# Control.net
KiCad netlist of a schematic drawn in Altium Designer
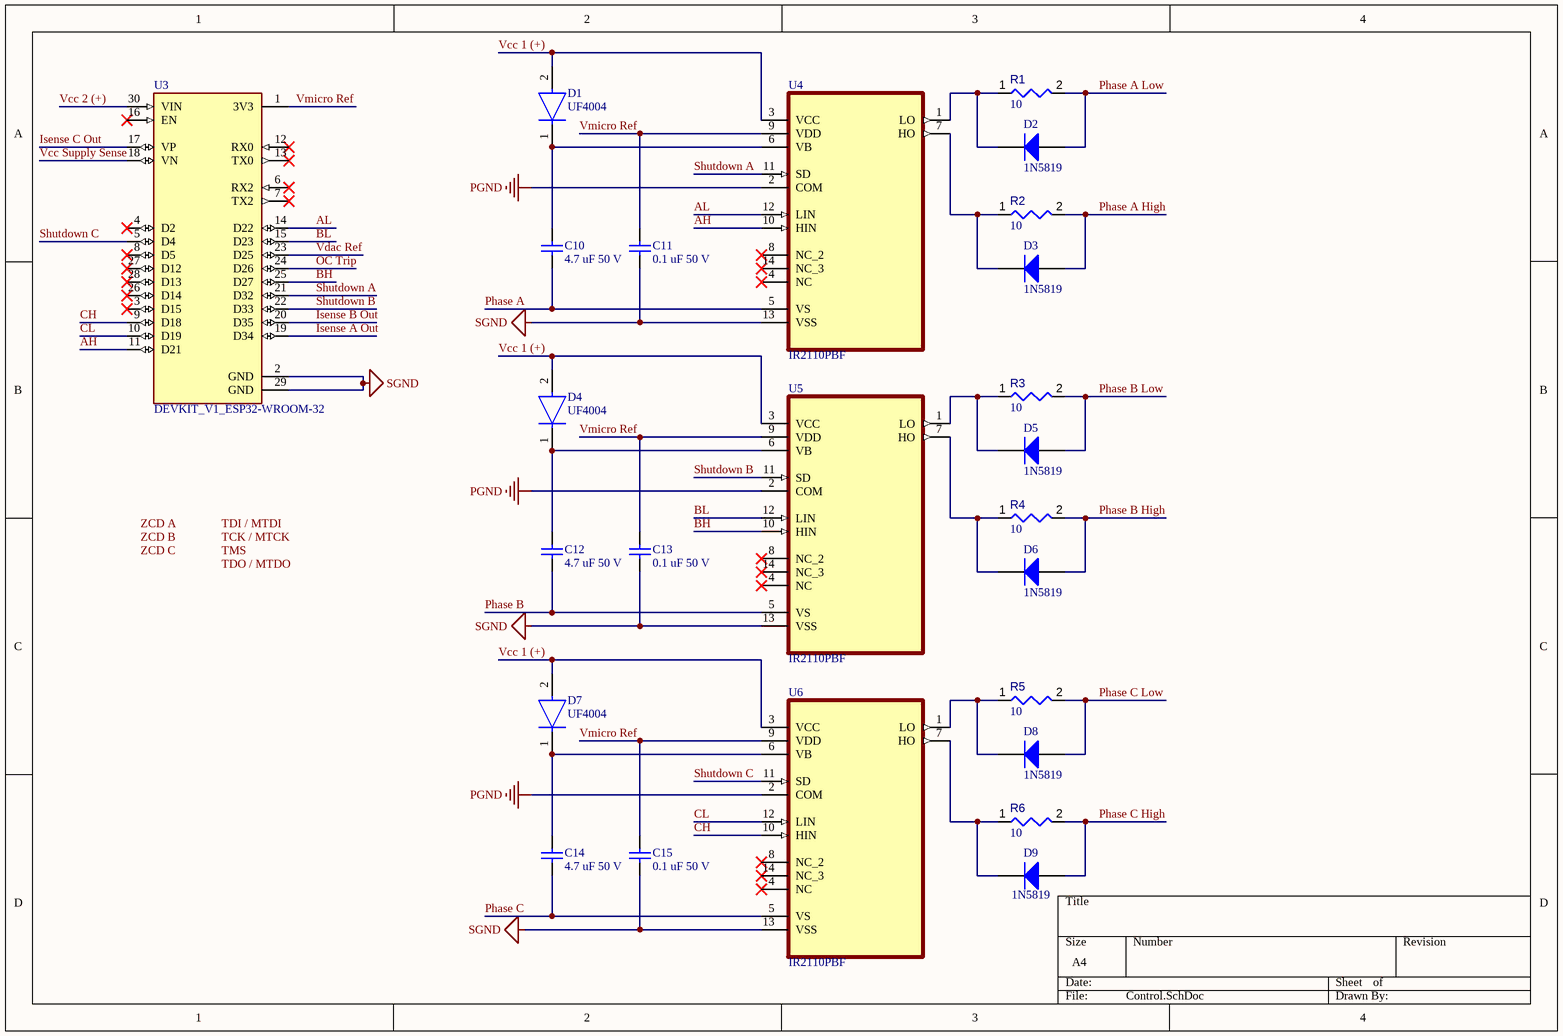
[diagram p0: Control.SchDoc]

(export (version "E")
  (design (tool "Eeschema 10.0.6"))
  (components
    (comp (ref "C10")
      (value "4.7 uF 50 V")
      (footprint "CAPR51-254-508X318X736")
      (libsource (lib "Altium Content Vault") (part "CAP-NP-2"))
    )
    (comp (ref "C11")
      (value "0.1 uF 50 V")
      (footprint "CAPR51-254-508X318X736")
      (libsource (lib "Altium Content Vault") (part "CAP-NP-2"))
    )
    (comp (ref "C12")
      (value "4.7 uF 50 V")
      (footprint "CAPR51-254-508X318X736")
      (libsource (lib "Altium Content Vault") (part "CAP-NP-2"))
    )
    (comp (ref "C13")
      (value "0.1 uF 50 V")
      (footprint "CAPR51-254-508X318X736")
      (libsource (lib "Altium Content Vault") (part "CAP-NP-2"))
    )
    (comp (ref "C14")
      (value "4.7 uF 50 V")
      (footprint "CAPR51-254-508X318X736")
      (libsource (lib "Altium Content Vault") (part "CAP-NP-2"))
    )
    (comp (ref "C15")
      (value "0.1 uF 50 V")
      (footprint "CAPR51-254-508X318X736")
      (libsource (lib "Altium Content Vault") (part "CAP-NP-2"))
    )
    (comp (ref "D1")
      (value "UF4004")
      (footprint "FP-017AH-MFG")
      (description "UF4004 Rectifier Diode, 1 Phase, 1 Element, 1A, 400V V(RRM), Silicon, DO-41")
      (libsource (lib "Altium Content Vault") (part "d7152d700b627762746794eb795d46e"))
    )
    (comp (ref "D2")
      (value "1N5819")
      (footprint "ONSC-AXIAL_LEAD-2-59-10_P")
      (description "Low Drop Power Schottky Rectifier, 40 V, 1 A, 2-Pin DO-41, RoHS")
      (fields (field (name "MANUFACTURER") "ON Semiconductor"))
      (libsource (lib "Pessoal") (part "D-AK-2"))
    )
    (comp (ref "D3")
      (value "1N5819")
      (footprint "ONSC-AXIAL_LEAD-2-59-10_P")
      (description "Low Drop Power Schottky Rectifier, 40 V, 1 A, 2-Pin DO-41, RoHS")
      (fields (field (name "MANUFACTURER") "ON Semiconductor"))
      (libsource (lib "Pessoal") (part "D-AK-2"))
    )
    (comp (ref "D4")
      (value "UF4004")
      (footprint "FP-017AH-MFG")
      (description "UF4004 Rectifier Diode, 1 Phase, 1 Element, 1A, 400V V(RRM), Silicon, DO-41")
      (libsource (lib "Altium Content Vault") (part "d7152d700b627762746794eb795d46e"))
    )
    (comp (ref "D5")
      (value "1N5819")
      (footprint "ONSC-AXIAL_LEAD-2-59-10_P")
      (description "Low Drop Power Schottky Rectifier, 40 V, 1 A, 2-Pin DO-41, RoHS")
      (fields (field (name "MANUFACTURER") "ON Semiconductor"))
      (libsource (lib "Pessoal") (part "D-AK-2"))
    )
    (comp (ref "D6")
      (value "1N5819")
      (footprint "ONSC-AXIAL_LEAD-2-59-10_P")
      (description "Low Drop Power Schottky Rectifier, 40 V, 1 A, 2-Pin DO-41, RoHS")
      (fields (field (name "MANUFACTURER") "ON Semiconductor"))
      (libsource (lib "Pessoal") (part "D-AK-2"))
    )
    (comp (ref "D7")
      (value "UF4004")
      (footprint "FP-017AH-MFG")
      (description "UF4004 Rectifier Diode, 1 Phase, 1 Element, 1A, 400V V(RRM), Silicon, DO-41")
      (libsource (lib "Altium Content Vault") (part "d7152d700b627762746794eb795d46e"))
    )
    (comp (ref "D8")
      (value "1N5819")
      (footprint "ONSC-AXIAL_LEAD-2-59-10_P")
      (description "Low Drop Power Schottky Rectifier, 40 V, 1 A, 2-Pin DO-41, RoHS")
      (fields (field (name "MANUFACTURER") "ON Semiconductor"))
      (libsource (lib "Pessoal") (part "D-AK-2"))
    )
    (comp (ref "D9")
      (value "1N5819")
      (footprint "ONSC-AXIAL_LEAD-2-59-10_P")
      (description "Low Drop Power Schottky Rectifier, 40 V, 1 A, 2-Pin DO-41, RoHS")
      (fields (field (name "MANUFACTURER") "ON Semiconductor"))
      (libsource (lib "Pessoal") (part "D-AK-2"))
    )
    (comp (ref "R1")
      (value "10")
      (footprint "RESA60-630X240")
      (description "10 Ohms ±1% 0.25W, 1/4W Through Hole Resistor Axial Metal Film")
      (fields (field (name "TOLERANCE") "1%") (field (name "POWER") "250mW"))
      (libsource (lib "Pessoal") (part "RES-2"))
    )
    (comp (ref "R2")
      (value "10")
      (footprint "RESA60-630X240")
      (description "10 Ohms ±1% 0.25W, 1/4W Through Hole Resistor Axial Metal Film")
      (fields (field (name "TOLERANCE") "1%") (field (name "POWER") "250mW"))
      (libsource (lib "Pessoal") (part "RES-2"))
    )
    (comp (ref "R3")
      (value "10")
      (footprint "RESA60-630X240")
      (description "10 Ohms ±1% 0.25W, 1/4W Through Hole Resistor Axial Metal Film")
      (fields (field (name "TOLERANCE") "1%") (field (name "POWER") "250mW"))
      (libsource (lib "Pessoal") (part "RES-2"))
    )
    (comp (ref "R4")
      (value "10")
      (footprint "RESA60-630X240")
      (description "10 Ohms ±1% 0.25W, 1/4W Through Hole Resistor Axial Metal Film")
      (fields (field (name "TOLERANCE") "1%") (field (name "POWER") "250mW"))
      (libsource (lib "Pessoal") (part "RES-2"))
    )
    (comp (ref "R5")
      (value "10")
      (footprint "RESA60-630X240")
      (description "10 Ohms ±1% 0.25W, 1/4W Through Hole Resistor Axial Metal Film")
      (fields (field (name "TOLERANCE") "1%") (field (name "POWER") "250mW"))
      (libsource (lib "Pessoal") (part "RES-2"))
    )
    (comp (ref "R6")
      (value "10")
      (footprint "RESA60-630X240")
      (description "10 Ohms ±1% 0.25W, 1/4W Through Hole Resistor Axial Metal Film")
      (fields (field (name "TOLERANCE") "1%") (field (name "POWER") "250mW"))
      (libsource (lib "Pessoal") (part "RES-2"))
    )
    (comp (ref "U3")
      (value "DEVKIT_V1_ESP32-WROOM-32")
      (footprint "MODULE_DEVKIT_V1_ESP32-WROOM-32")
      (description "WROOM-32 Development Board ESP32 ESP-32S WiFi Bluetooth Dev Module")
      (fields (field (name "MF") "Do it") (field (name "MP") "DEVKIT V1 ESP32-WROOM-32"))
      (libsource (lib "DEVKIT_V1_ESP32-WROOM-32") (part "DEVKIT_V1_ESP32-WROOM-32"))
    )
    (comp (ref "U4")
      (value "IR2110PBF")
      (footprint "DIP254P762X533-14")
      (fields (field (name "MF") "Infineon"))
      (libsource (lib "IR2110PBF") (part "IR2110PBF"))
    )
    (comp (ref "U5")
      (value "IR2110PBF")
      (footprint "DIP254P762X533-14")
      (fields (field (name "MF") "Infineon"))
      (libsource (lib "IR2110PBF") (part "IR2110PBF"))
    )
    (comp (ref "U6")
      (value "IR2110PBF")
      (footprint "DIP254P762X533-14")
      (fields (field (name "MF") "Infineon"))
      (libsource (lib "IR2110PBF") (part "IR2110PBF"))
    )
  )
  (nets
    (net (code "1") (name "/AH") (class "Default")
      (node (ref "U3") (pin "11") (pinfunction "D21_11") (pintype "bidirectional"))
      (node (ref "U4") (pin "10") (pinfunction "HIN_10") (pintype "input"))
    )
    (net (code "2") (name "/AL") (class "Default")
      (node (ref "U3") (pin "14") (pinfunction "D22_14") (pintype "bidirectional"))
      (node (ref "U4") (pin "12") (pinfunction "LIN_12") (pintype "input"))
    )
    (net (code "3") (name "/BH") (class "Default")
      (node (ref "U3") (pin "25") (pinfunction "D27_25") (pintype "bidirectional"))
      (node (ref "U5") (pin "10") (pinfunction "HIN_10") (pintype "input"))
    )
    (net (code "4") (name "/BL") (class "Default")
      (node (ref "U3") (pin "15") (pinfunction "D23_15") (pintype "bidirectional"))
      (node (ref "U5") (pin "12") (pinfunction "LIN_12") (pintype "input"))
    )
    (net (code "5") (name "/CH") (class "Default")
      (node (ref "U3") (pin "9") (pinfunction "D18_9") (pintype "bidirectional"))
      (node (ref "U6") (pin "10") (pinfunction "HIN_10") (pintype "input"))
    )
    (net (code "6") (name "/CL") (class "Default")
      (node (ref "U3") (pin "10") (pinfunction "D19_10") (pintype "bidirectional"))
      (node (ref "U6") (pin "12") (pinfunction "LIN_12") (pintype "input"))
    )
    (net (code "7") (name "/Isense A Out") (class "Default")
      (node (ref "U3") (pin "19") (pinfunction "D34_19") (pintype "bidirectional"))
    )
    (net (code "8") (name "/Isense B Out") (class "Default")
      (node (ref "U3") (pin "20") (pinfunction "D35_20") (pintype "bidirectional"))
    )
    (net (code "9") (name "/Isense C Out") (class "Default")
      (node (ref "U3") (pin "17") (pinfunction "VP_17") (pintype "bidirectional"))
    )
    (net (code "10") (name "/OC Trip") (class "Default")
      (node (ref "U3") (pin "24") (pinfunction "D26_24") (pintype "bidirectional"))
    )
    (net (code "11") (name "/Phase A") (class "Default")
      (node (ref "C10") (pin "1") (pinfunction "1_1") (pintype "passive"))
      (node (ref "U4") (pin "5") (pinfunction "VS_5") (pintype "power_in"))
    )
    (net (code "12") (name "/Phase A High") (class "Default")
      (node (ref "D3") (pin "1") (pinfunction "A_1") (pintype "passive"))
      (node (ref "R2") (pin "2") (pinfunction "2_2") (pintype "passive"))
    )
    (net (code "13") (name "/Phase A Low") (class "Default")
      (node (ref "D2") (pin "1") (pinfunction "A_1") (pintype "passive"))
      (node (ref "R1") (pin "2") (pinfunction "2_2") (pintype "passive"))
    )
    (net (code "14") (name "/Phase B") (class "Default")
      (node (ref "C12") (pin "1") (pinfunction "1_1") (pintype "passive"))
      (node (ref "U5") (pin "5") (pinfunction "VS_5") (pintype "power_in"))
    )
    (net (code "15") (name "/Phase B High") (class "Default")
      (node (ref "D6") (pin "1") (pinfunction "A_1") (pintype "passive"))
      (node (ref "R4") (pin "2") (pinfunction "2_2") (pintype "passive"))
    )
    (net (code "16") (name "/Phase B Low") (class "Default")
      (node (ref "D5") (pin "1") (pinfunction "A_1") (pintype "passive"))
      (node (ref "R3") (pin "2") (pinfunction "2_2") (pintype "passive"))
    )
    (net (code "17") (name "/Phase C") (class "Default")
      (node (ref "C14") (pin "1") (pinfunction "1_1") (pintype "passive"))
      (node (ref "U6") (pin "5") (pinfunction "VS_5") (pintype "power_in"))
    )
    (net (code "18") (name "/Phase C High") (class "Default")
      (node (ref "D9") (pin "1") (pinfunction "A_1") (pintype "passive"))
      (node (ref "R6") (pin "2") (pinfunction "2_2") (pintype "passive"))
    )
    (net (code "19") (name "/Phase C Low") (class "Default")
      (node (ref "D8") (pin "1") (pinfunction "A_1") (pintype "passive"))
      (node (ref "R5") (pin "2") (pinfunction "2_2") (pintype "passive"))
    )
    (net (code "20") (name "/Shutdown A") (class "Default")
      (node (ref "U3") (pin "21") (pinfunction "D32_21") (pintype "bidirectional"))
      (node (ref "U4") (pin "11") (pinfunction "SD_11") (pintype "input"))
    )
    (net (code "21") (name "/Shutdown B") (class "Default")
      (node (ref "U3") (pin "22") (pinfunction "D33_22") (pintype "bidirectional"))
      (node (ref "U5") (pin "11") (pinfunction "SD_11") (pintype "input"))
    )
    (net (code "22") (name "/Shutdown C") (class "Default")
      (node (ref "U3") (pin "5") (pinfunction "D4_5") (pintype "bidirectional"))
      (node (ref "U6") (pin "11") (pinfunction "SD_11") (pintype "input"))
    )
    (net (code "27") (name "/Vcc 1 (+)") (class "Default")
      (node (ref "D1") (pin "2") (pinfunction "A_2") (pintype "passive"))
      (node (ref "D4") (pin "2") (pinfunction "A_2") (pintype "passive"))
      (node (ref "D7") (pin "2") (pinfunction "A_2") (pintype "passive"))
      (node (ref "U4") (pin "3") (pinfunction "VCC_3") (pintype "power_in"))
      (node (ref "U5") (pin "3") (pinfunction "VCC_3") (pintype "power_in"))
      (node (ref "U6") (pin "3") (pinfunction "VCC_3") (pintype "power_in"))
    )
    (net (code "28") (name "/Vcc 2 (+)") (class "Default")
      (node (ref "U3") (pin "30") (pinfunction "VIN_30") (pintype "input"))
    )
    (net (code "29") (name "/Vcc Supply Sense") (class "Default")
      (node (ref "U3") (pin "18") (pinfunction "VN_18") (pintype "bidirectional"))
    )
    (net (code "30") (name "/Vdac Ref") (class "Default")
      (node (ref "U3") (pin "23") (pinfunction "D25_23") (pintype "bidirectional"))
    )
    (net (code "31") (name "/Vmicro Ref") (class "Default")
      (node (ref "C11") (pin "2") (pinfunction "2_2") (pintype "passive"))
      (node (ref "C13") (pin "2") (pinfunction "2_2") (pintype "passive"))
      (node (ref "C15") (pin "2") (pinfunction "2_2") (pintype "passive"))
      (node (ref "U3") (pin "1") (pinfunction "3V3_1") (pintype "power_in"))
      (node (ref "U4") (pin "9") (pinfunction "VDD_9") (pintype "power_in"))
      (node (ref "U5") (pin "9") (pinfunction "VDD_9") (pintype "power_in"))
      (node (ref "U6") (pin "9") (pinfunction "VDD_9") (pintype "power_in"))
    )
    (net (code "35") (name "Net-(D1-C)") (class "Default")
      (node (ref "C10") (pin "2") (pinfunction "2_2") (pintype "passive"))
      (node (ref "D1") (pin "1") (pinfunction "C_1") (pintype "passive"))
      (node (ref "U4") (pin "6") (pinfunction "VB_6") (pintype "power_in"))
    )
    (net (code "36") (name "Net-(D2-K)") (class "Default")
      (node (ref "D2") (pin "2") (pinfunction "K_2") (pintype "passive"))
      (node (ref "R1") (pin "1") (pinfunction "1_1") (pintype "passive"))
      (node (ref "U4") (pin "1") (pinfunction "LO_1") (pintype "output"))
    )
    (net (code "37") (name "Net-(D3-K)") (class "Default")
      (node (ref "D3") (pin "2") (pinfunction "K_2") (pintype "passive"))
      (node (ref "R2") (pin "1") (pinfunction "1_1") (pintype "passive"))
      (node (ref "U4") (pin "7") (pinfunction "HO_7") (pintype "output"))
    )
    (net (code "38") (name "Net-(D4-C)") (class "Default")
      (node (ref "C12") (pin "2") (pinfunction "2_2") (pintype "passive"))
      (node (ref "D4") (pin "1") (pinfunction "C_1") (pintype "passive"))
      (node (ref "U5") (pin "6") (pinfunction "VB_6") (pintype "power_in"))
    )
    (net (code "39") (name "Net-(D5-K)") (class "Default")
      (node (ref "D5") (pin "2") (pinfunction "K_2") (pintype "passive"))
      (node (ref "R3") (pin "1") (pinfunction "1_1") (pintype "passive"))
      (node (ref "U5") (pin "1") (pinfunction "LO_1") (pintype "output"))
    )
    (net (code "40") (name "Net-(D6-K)") (class "Default")
      (node (ref "D6") (pin "2") (pinfunction "K_2") (pintype "passive"))
      (node (ref "R4") (pin "1") (pinfunction "1_1") (pintype "passive"))
      (node (ref "U5") (pin "7") (pinfunction "HO_7") (pintype "output"))
    )
    (net (code "41") (name "Net-(D7-C)") (class "Default")
      (node (ref "C14") (pin "2") (pinfunction "2_2") (pintype "passive"))
      (node (ref "D7") (pin "1") (pinfunction "C_1") (pintype "passive"))
      (node (ref "U6") (pin "6") (pinfunction "VB_6") (pintype "power_in"))
    )
    (net (code "42") (name "Net-(D8-K)") (class "Default")
      (node (ref "D8") (pin "2") (pinfunction "K_2") (pintype "passive"))
      (node (ref "R5") (pin "1") (pinfunction "1_1") (pintype "passive"))
      (node (ref "U6") (pin "1") (pinfunction "LO_1") (pintype "output"))
    )
    (net (code "43") (name "Net-(D9-K)") (class "Default")
      (node (ref "D9") (pin "2") (pinfunction "K_2") (pintype "passive"))
      (node (ref "R6") (pin "1") (pinfunction "1_1") (pintype "passive"))
      (node (ref "U6") (pin "7") (pinfunction "HO_7") (pintype "output"))
    )
    (net (code "44") (name "PGND") (class "Default")
      (node (ref "U4") (pin "2") (pinfunction "COM_2") (pintype "passive"))
      (node (ref "U5") (pin "2") (pinfunction "COM_2") (pintype "passive"))
      (node (ref "U6") (pin "2") (pinfunction "COM_2") (pintype "passive"))
    )
    (net (code "45") (name "SGND") (class "Default")
      (node (ref "C11") (pin "1") (pinfunction "1_1") (pintype "passive"))
      (node (ref "C13") (pin "1") (pinfunction "1_1") (pintype "passive"))
      (node (ref "C15") (pin "1") (pinfunction "1_1") (pintype "passive"))
      (node (ref "U3") (pin "2") (pinfunction "GND_2") (pintype "power_in"))
      (node (ref "U3") (pin "29") (pinfunction "GND_29") (pintype "power_in"))
      (node (ref "U4") (pin "13") (pinfunction "VSS_13") (pintype "power_in"))
      (node (ref "U5") (pin "13") (pinfunction "VSS_13") (pintype "power_in"))
      (node (ref "U6") (pin "13") (pinfunction "VSS_13") (pintype "power_in"))
    )
    (net (code "46") (name "unconnected-(U3-D2-Pad4)") (class "Default")
      (node (ref "U3") (pin "4") (pinfunction "D2_4") (pintype "bidirectional+no_connect"))
    )
    (net (code "47") (name "unconnected-(U3-D5-Pad8)") (class "Default")
      (node (ref "U3") (pin "8") (pinfunction "D5_8") (pintype "bidirectional+no_connect"))
    )
    (net (code "48") (name "unconnected-(U3-D12-Pad27)") (class "Default")
      (node (ref "U3") (pin "27") (pinfunction "D12_27") (pintype "bidirectional+no_connect"))
    )
    (net (code "49") (name "unconnected-(U3-D13-Pad28)") (class "Default")
      (node (ref "U3") (pin "28") (pinfunction "D13_28") (pintype "bidirectional+no_connect"))
    )
    (net (code "50") (name "unconnected-(U3-D14-Pad26)") (class "Default")
      (node (ref "U3") (pin "26") (pinfunction "D14_26") (pintype "bidirectional+no_connect"))
    )
    (net (code "51") (name "unconnected-(U3-D15-Pad3)") (class "Default")
      (node (ref "U3") (pin "3") (pinfunction "D15_3") (pintype "bidirectional+no_connect"))
    )
    (net (code "52") (name "unconnected-(U3-EN-Pad16)") (class "Default")
      (node (ref "U3") (pin "16") (pinfunction "EN_16") (pintype "input+no_connect"))
    )
    (net (code "53") (name "unconnected-(U3-RX0-Pad12)") (class "Default")
      (node (ref "U3") (pin "12") (pinfunction "RX0_12") (pintype "input+no_connect"))
    )
    (net (code "54") (name "unconnected-(U3-RX2-Pad6)") (class "Default")
      (node (ref "U3") (pin "6") (pinfunction "RX2_6") (pintype "input+no_connect"))
    )
    (net (code "55") (name "unconnected-(U3-TX0-Pad13)") (class "Default")
      (node (ref "U3") (pin "13") (pinfunction "TX0_13") (pintype "output+no_connect"))
    )
    (net (code "56") (name "unconnected-(U3-TX2-Pad7)") (class "Default")
      (node (ref "U3") (pin "7") (pinfunction "TX2_7") (pintype "output+no_connect"))
    )
    (net (code "57") (name "unconnected-(U4-NC-Pad4)") (class "Default")
      (node (ref "U4") (pin "4") (pinfunction "NC_4") (pintype "passive+no_connect"))
    )
    (net (code "58") (name "unconnected-(U4-NC_2-Pad8)") (class "Default")
      (node (ref "U4") (pin "8") (pinfunction "NC_2_8") (pintype "passive+no_connect"))
    )
    (net (code "59") (name "unconnected-(U4-NC_3-Pad14)") (class "Default")
      (node (ref "U4") (pin "14") (pinfunction "NC_3_14") (pintype "passive+no_connect"))
    )
    (net (code "60") (name "unconnected-(U5-NC-Pad4)") (class "Default")
      (node (ref "U5") (pin "4") (pinfunction "NC_4") (pintype "passive+no_connect"))
    )
    (net (code "61") (name "unconnected-(U5-NC_2-Pad8)") (class "Default")
      (node (ref "U5") (pin "8") (pinfunction "NC_2_8") (pintype "passive+no_connect"))
    )
    (net (code "62") (name "unconnected-(U5-NC_3-Pad14)") (class "Default")
      (node (ref "U5") (pin "14") (pinfunction "NC_3_14") (pintype "passive+no_connect"))
    )
    (net (code "63") (name "unconnected-(U6-NC-Pad4)") (class "Default")
      (node (ref "U6") (pin "4") (pinfunction "NC_4") (pintype "passive+no_connect"))
    )
    (net (code "64") (name "unconnected-(U6-NC_2-Pad8)") (class "Default")
      (node (ref "U6") (pin "8") (pinfunction "NC_2_8") (pintype "passive+no_connect"))
    )
    (net (code "65") (name "unconnected-(U6-NC_3-Pad14)") (class "Default")
      (node (ref "U6") (pin "14") (pinfunction "NC_3_14") (pintype "passive+no_connect"))
    )
  )
)
